# Relay220VAC.net
KiCad netlist of a schematic drawn in Altium Designer
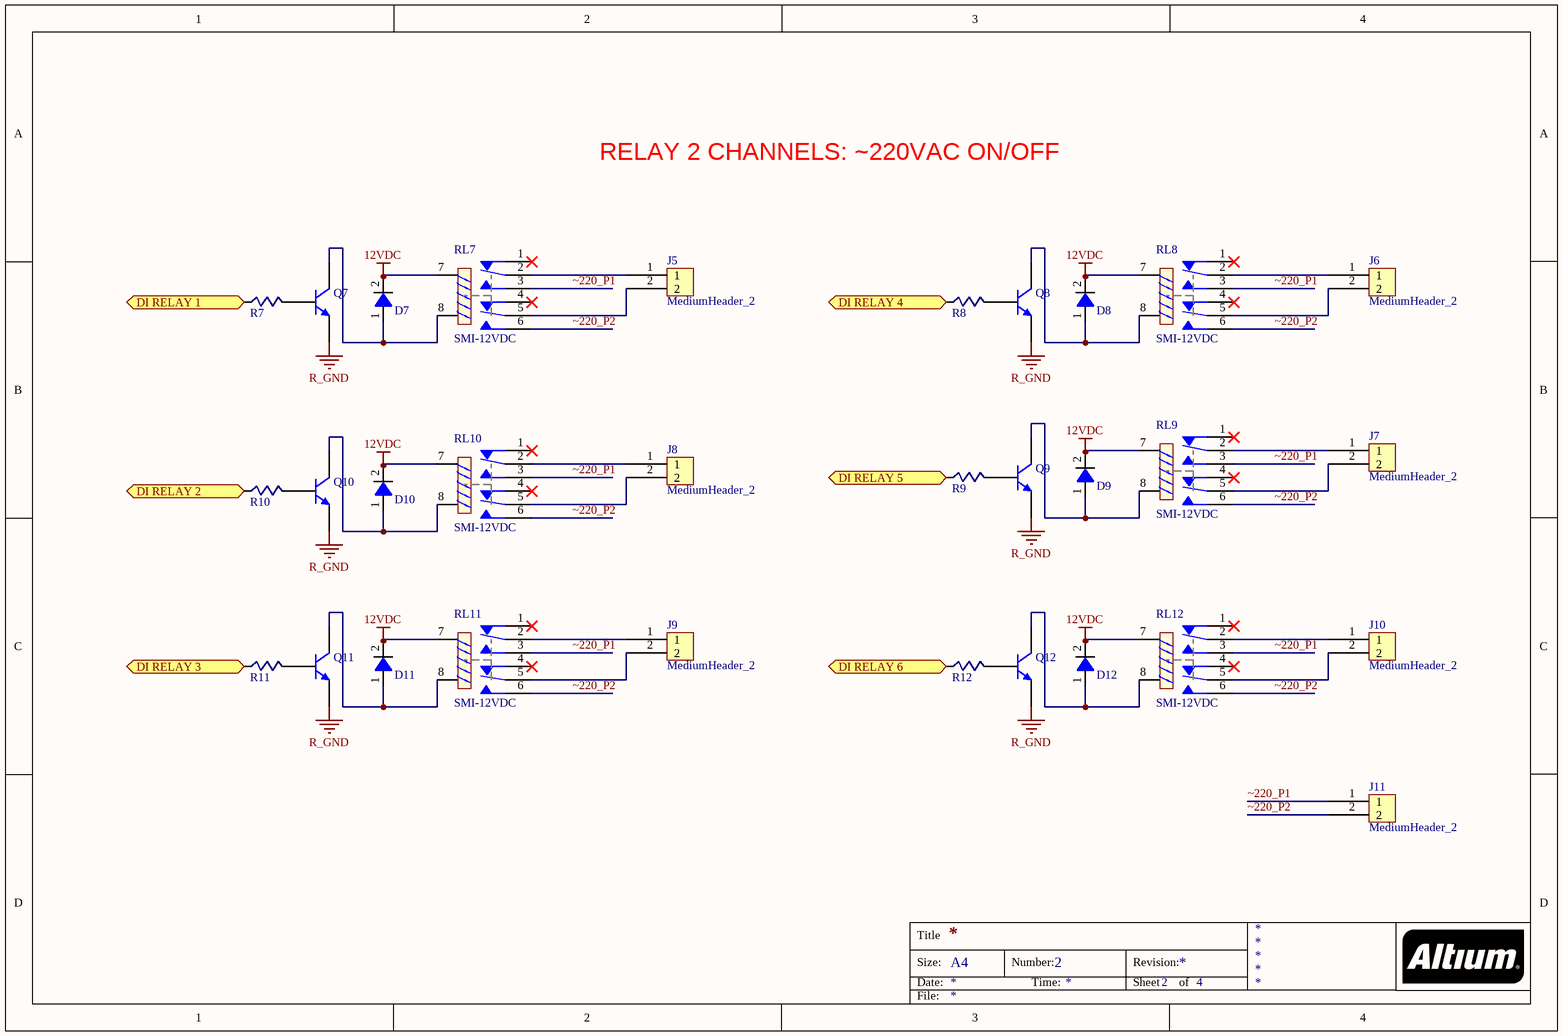
[diagram p0: Relay220VAC.SchDoc]

(export (version "E")
  (design (tool "Eeschema 10.0.6"))
  (components
    (comp (ref "D7")
      (value "M7 SMD")
      (footprint "Diode 1N4007 SMD")
      (description "DIODE GEN PURP 1KV 1A DO214AC")
      (libsource (lib "EngineersLife") (part "Diode_1N4007"))
    )
    (comp (ref "D8")
      (value "M7 SMD")
      (footprint "Diode 1N4007 SMD")
      (description "DIODE GEN PURP 1KV 1A DO214AC")
      (libsource (lib "EngineersLife") (part "Diode_1N4007"))
    )
    (comp (ref "D9")
      (value "M7 SMD")
      (footprint "Diode 1N4007 SMD")
      (description "DIODE GEN PURP 1KV 1A DO214AC")
      (libsource (lib "EngineersLife") (part "Diode_1N4007"))
    )
    (comp (ref "D10")
      (value "M7 SMD")
      (footprint "Diode 1N4007 SMD")
      (description "DIODE GEN PURP 1KV 1A DO214AC")
      (libsource (lib "EngineersLife") (part "Diode_1N4007"))
    )
    (comp (ref "D11")
      (value "M7 SMD")
      (footprint "Diode 1N4007 SMD")
      (description "DIODE GEN PURP 1KV 1A DO214AC")
      (libsource (lib "EngineersLife") (part "Diode_1N4007"))
    )
    (comp (ref "D12")
      (value "M7 SMD")
      (footprint "Diode 1N4007 SMD")
      (description "DIODE GEN PURP 1KV 1A DO214AC")
      (libsource (lib "EngineersLife") (part "Diode_1N4007"))
    )
    (comp (ref "J5")
      (value "MediumHeader_2")
      (footprint "Medium - Header 2")
      (libsource (lib "EngineersLife") (part "MediumHeader_2"))
    )
    (comp (ref "J6")
      (value "MediumHeader_2")
      (footprint "Medium - Header 2")
      (libsource (lib "EngineersLife") (part "MediumHeader_2"))
    )
    (comp (ref "J7")
      (value "MediumHeader_2")
      (footprint "Medium - Header 2")
      (libsource (lib "EngineersLife") (part "MediumHeader_2"))
    )
    (comp (ref "J8")
      (value "MediumHeader_2")
      (footprint "Medium - Header 2")
      (libsource (lib "EngineersLife") (part "MediumHeader_2"))
    )
    (comp (ref "J9")
      (value "MediumHeader_2")
      (footprint "Medium - Header 2")
      (libsource (lib "EngineersLife") (part "MediumHeader_2"))
    )
    (comp (ref "J10")
      (value "MediumHeader_2")
      (footprint "Medium - Header 2")
      (libsource (lib "EngineersLife") (part "MediumHeader_2"))
    )
    (comp (ref "J11")
      (value "MediumHeader_2")
      (footprint "Medium - Header 2")
      (libsource (lib "EngineersLife") (part "MediumHeader_2"))
    )
    (comp (ref "Q7")
      (value "MMBT3904")
      (footprint "SOT23_L_MOD")
      (description "TRANSISTOR GP NPN AMP SOT-23")
      (fields (field (name "PUBLISHER") "Altium Limited"))
      (libsource (lib "EngineersLife") (part "MMBT3904"))
    )
    (comp (ref "Q8")
      (value "MMBT3904")
      (footprint "SOT23_L_MOD")
      (description "TRANSISTOR GP NPN AMP SOT-23")
      (fields (field (name "PUBLISHER") "Altium Limited"))
      (libsource (lib "EngineersLife") (part "MMBT3904"))
    )
    (comp (ref "Q9")
      (value "MMBT3904")
      (footprint "SOT23_L_MOD")
      (description "TRANSISTOR GP NPN AMP SOT-23")
      (fields (field (name "PUBLISHER") "Altium Limited"))
      (libsource (lib "EngineersLife") (part "MMBT3904"))
    )
    (comp (ref "Q10")
      (value "MMBT3904")
      (footprint "SOT23_L_MOD")
      (description "TRANSISTOR GP NPN AMP SOT-23")
      (fields (field (name "PUBLISHER") "Altium Limited"))
      (libsource (lib "EngineersLife") (part "MMBT3904"))
    )
    (comp (ref "Q11")
      (value "MMBT3904")
      (footprint "SOT23_L_MOD")
      (description "TRANSISTOR GP NPN AMP SOT-23")
      (fields (field (name "PUBLISHER") "Altium Limited"))
      (libsource (lib "EngineersLife") (part "MMBT3904"))
    )
    (comp (ref "Q12")
      (value "MMBT3904")
      (footprint "SOT23_L_MOD")
      (description "TRANSISTOR GP NPN AMP SOT-23")
      (fields (field (name "PUBLISHER") "Altium Limited"))
      (libsource (lib "EngineersLife") (part "MMBT3904"))
    )
    (comp (ref "R7")
      (value "R_1K_0603")
      (footprint "RES-SMD-0603")
      (description "RES 1K OHM 1/10W 1% 0603 SMD")
      (libsource (lib "EngineersLife") (part "RES0603_1K"))
    )
    (comp (ref "R8")
      (value "R_1K_0603")
      (footprint "RES-SMD-0603")
      (description "RES 1K OHM 1/10W 1% 0603 SMD")
      (libsource (lib "EngineersLife") (part "RES0603_1K"))
    )
    (comp (ref "R9")
      (value "R_1K_0603")
      (footprint "RES-SMD-0603")
      (description "RES 1K OHM 1/10W 1% 0603 SMD")
      (libsource (lib "EngineersLife") (part "RES0603_1K"))
    )
    (comp (ref "R10")
      (value "R_1K_0603")
      (footprint "RES-SMD-0603")
      (description "RES 1K OHM 1/10W 1% 0603 SMD")
      (libsource (lib "EngineersLife") (part "RES0603_1K"))
    )
    (comp (ref "R11")
      (value "R_1K_0603")
      (footprint "RES-SMD-0603")
      (description "RES 1K OHM 1/10W 1% 0603 SMD")
      (libsource (lib "EngineersLife") (part "RES0603_1K"))
    )
    (comp (ref "R12")
      (value "R_1K_0603")
      (footprint "RES-SMD-0603")
      (description "RES 1K OHM 1/10W 1% 0603 SMD")
      (libsource (lib "EngineersLife") (part "RES0603_1K"))
    )
    (comp (ref "RL7")
      (value "SMI-12VDC")
      (footprint "RELAY SMI-2P")
      (description "Relay 12VDC, 2 channel")
      (libsource (lib "EngineersLife") (part "RELAY SMI-2P"))
    )
    (comp (ref "RL8")
      (value "SMI-12VDC")
      (footprint "RELAY SMI-2P")
      (description "Relay 12VDC, 2 channel")
      (libsource (lib "EngineersLife") (part "RELAY SMI-2P"))
    )
    (comp (ref "RL9")
      (value "SMI-12VDC")
      (footprint "RELAY SMI-2P")
      (description "Relay 12VDC, 2 channel")
      (libsource (lib "EngineersLife") (part "RELAY SMI-2P"))
    )
    (comp (ref "RL10")
      (value "SMI-12VDC")
      (footprint "RELAY SMI-2P")
      (description "Relay 12VDC, 2 channel")
      (libsource (lib "EngineersLife") (part "RELAY SMI-2P"))
    )
    (comp (ref "RL11")
      (value "SMI-12VDC")
      (footprint "RELAY SMI-2P")
      (description "Relay 12VDC, 2 channel")
      (libsource (lib "EngineersLife") (part "RELAY SMI-2P"))
    )
    (comp (ref "RL12")
      (value "SMI-12VDC")
      (footprint "RELAY SMI-2P")
      (description "Relay 12VDC, 2 channel")
      (libsource (lib "EngineersLife") (part "RELAY SMI-2P"))
    )
  )
  (nets
    (net (code "1") (name "/DI RELAY 1") (class "Default")
      (node (ref "R7") (pin "1") (pinfunction "1_1") (pintype "passive"))
    )
    (net (code "2") (name "/DI RELAY 2") (class "Default")
      (node (ref "R10") (pin "1") (pinfunction "1_1") (pintype "passive"))
    )
    (net (code "3") (name "/DI RELAY 3") (class "Default")
      (node (ref "R11") (pin "1") (pinfunction "1_1") (pintype "passive"))
    )
    (net (code "4") (name "/DI RELAY 4") (class "Default")
      (node (ref "R8") (pin "1") (pinfunction "1_1") (pintype "passive"))
    )
    (net (code "5") (name "/DI RELAY 5") (class "Default")
      (node (ref "R9") (pin "1") (pinfunction "1_1") (pintype "passive"))
    )
    (net (code "6") (name "/DI RELAY 6") (class "Default")
      (node (ref "R12") (pin "1") (pinfunction "1_1") (pintype "passive"))
    )
    (net (code "7") (name "/~220_P1") (class "Default")
      (node (ref "J11") (pin "1") (pinfunction "1_1") (pintype "passive"))
      (node (ref "RL10") (pin "3") (pinfunction "3_3") (pintype "passive"))
      (node (ref "RL11") (pin "3") (pinfunction "3_3") (pintype "passive"))
      (node (ref "RL12") (pin "3") (pinfunction "3_3") (pintype "passive"))
      (node (ref "RL7") (pin "3") (pinfunction "3_3") (pintype "passive"))
      (node (ref "RL8") (pin "3") (pinfunction "3_3") (pintype "passive"))
      (node (ref "RL9") (pin "3") (pinfunction "3_3") (pintype "passive"))
    )
    (net (code "8") (name "/~220_P2") (class "Default")
      (node (ref "J11") (pin "2") (pinfunction "2_2") (pintype "passive"))
      (node (ref "RL10") (pin "6") (pinfunction "6_6") (pintype "passive"))
      (node (ref "RL11") (pin "6") (pinfunction "6_6") (pintype "passive"))
      (node (ref "RL12") (pin "6") (pinfunction "6_6") (pintype "passive"))
      (node (ref "RL7") (pin "6") (pinfunction "6_6") (pintype "passive"))
      (node (ref "RL8") (pin "6") (pinfunction "6_6") (pintype "passive"))
      (node (ref "RL9") (pin "6") (pinfunction "6_6") (pintype "passive"))
    )
    (net (code "9") (name "12VDC") (class "Default")
      (node (ref "D10") (pin "2") (pinfunction "4_2") (pintype "passive"))
      (node (ref "D11") (pin "2") (pinfunction "4_2") (pintype "passive"))
      (node (ref "D12") (pin "2") (pinfunction "4_2") (pintype "passive"))
      (node (ref "D7") (pin "2") (pinfunction "4_2") (pintype "passive"))
      (node (ref "D8") (pin "2") (pinfunction "4_2") (pintype "passive"))
      (node (ref "D9") (pin "2") (pinfunction "4_2") (pintype "passive"))
      (node (ref "RL10") (pin "7") (pinfunction "7_7") (pintype "passive"))
      (node (ref "RL11") (pin "7") (pinfunction "7_7") (pintype "passive"))
      (node (ref "RL12") (pin "7") (pinfunction "7_7") (pintype "passive"))
      (node (ref "RL7") (pin "7") (pinfunction "7_7") (pintype "passive"))
      (node (ref "RL8") (pin "7") (pinfunction "7_7") (pintype "passive"))
      (node (ref "RL9") (pin "7") (pinfunction "7_7") (pintype "passive"))
    )
    (net (code "10") (name "Net-(D7-3)") (class "Default")
      (node (ref "D7") (pin "1") (pinfunction "3_1") (pintype "passive"))
      (node (ref "Q7") (pin "3") (pinfunction "C_3") (pintype "passive"))
      (node (ref "RL7") (pin "8") (pinfunction "8_8") (pintype "passive"))
    )
    (net (code "11") (name "Net-(D8-3)") (class "Default")
      (node (ref "D8") (pin "1") (pinfunction "3_1") (pintype "passive"))
      (node (ref "Q8") (pin "3") (pinfunction "C_3") (pintype "passive"))
      (node (ref "RL8") (pin "8") (pinfunction "8_8") (pintype "passive"))
    )
    (net (code "12") (name "Net-(D9-3)") (class "Default")
      (node (ref "D9") (pin "1") (pinfunction "3_1") (pintype "passive"))
      (node (ref "Q9") (pin "3") (pinfunction "C_3") (pintype "passive"))
      (node (ref "RL9") (pin "8") (pinfunction "8_8") (pintype "passive"))
    )
    (net (code "13") (name "Net-(D10-3)") (class "Default")
      (node (ref "D10") (pin "1") (pinfunction "3_1") (pintype "passive"))
      (node (ref "Q10") (pin "3") (pinfunction "C_3") (pintype "passive"))
      (node (ref "RL10") (pin "8") (pinfunction "8_8") (pintype "passive"))
    )
    (net (code "14") (name "Net-(D11-3)") (class "Default")
      (node (ref "D11") (pin "1") (pinfunction "3_1") (pintype "passive"))
      (node (ref "Q11") (pin "3") (pinfunction "C_3") (pintype "passive"))
      (node (ref "RL11") (pin "8") (pinfunction "8_8") (pintype "passive"))
    )
    (net (code "15") (name "Net-(D12-3)") (class "Default")
      (node (ref "D12") (pin "1") (pinfunction "3_1") (pintype "passive"))
      (node (ref "Q12") (pin "3") (pinfunction "C_3") (pintype "passive"))
      (node (ref "RL12") (pin "8") (pinfunction "8_8") (pintype "passive"))
    )
    (net (code "16") (name "Net-(J5-Pad1)") (class "Default")
      (node (ref "J5") (pin "1") (pinfunction "1_1") (pintype "passive"))
      (node (ref "RL7") (pin "2") (pinfunction "2_2") (pintype "passive"))
    )
    (net (code "17") (name "Net-(J5-Pad2)") (class "Default")
      (node (ref "J5") (pin "2") (pinfunction "2_2") (pintype "passive"))
      (node (ref "RL7") (pin "5") (pinfunction "5_5") (pintype "passive"))
    )
    (net (code "18") (name "Net-(J6-Pad1)") (class "Default")
      (node (ref "J6") (pin "1") (pinfunction "1_1") (pintype "passive"))
      (node (ref "RL8") (pin "2") (pinfunction "2_2") (pintype "passive"))
    )
    (net (code "19") (name "Net-(J6-Pad2)") (class "Default")
      (node (ref "J6") (pin "2") (pinfunction "2_2") (pintype "passive"))
      (node (ref "RL8") (pin "5") (pinfunction "5_5") (pintype "passive"))
    )
    (net (code "20") (name "Net-(J7-Pad1)") (class "Default")
      (node (ref "J7") (pin "1") (pinfunction "1_1") (pintype "passive"))
      (node (ref "RL9") (pin "2") (pinfunction "2_2") (pintype "passive"))
    )
    (net (code "21") (name "Net-(J7-Pad2)") (class "Default")
      (node (ref "J7") (pin "2") (pinfunction "2_2") (pintype "passive"))
      (node (ref "RL9") (pin "5") (pinfunction "5_5") (pintype "passive"))
    )
    (net (code "22") (name "Net-(J8-Pad1)") (class "Default")
      (node (ref "J8") (pin "1") (pinfunction "1_1") (pintype "passive"))
      (node (ref "RL10") (pin "2") (pinfunction "2_2") (pintype "passive"))
    )
    (net (code "23") (name "Net-(J8-Pad2)") (class "Default")
      (node (ref "J8") (pin "2") (pinfunction "2_2") (pintype "passive"))
      (node (ref "RL10") (pin "5") (pinfunction "5_5") (pintype "passive"))
    )
    (net (code "24") (name "Net-(J9-Pad1)") (class "Default")
      (node (ref "J9") (pin "1") (pinfunction "1_1") (pintype "passive"))
      (node (ref "RL11") (pin "2") (pinfunction "2_2") (pintype "passive"))
    )
    (net (code "25") (name "Net-(J9-Pad2)") (class "Default")
      (node (ref "J9") (pin "2") (pinfunction "2_2") (pintype "passive"))
      (node (ref "RL11") (pin "5") (pinfunction "5_5") (pintype "passive"))
    )
    (net (code "26") (name "Net-(J10-Pad1)") (class "Default")
      (node (ref "J10") (pin "1") (pinfunction "1_1") (pintype "passive"))
      (node (ref "RL12") (pin "2") (pinfunction "2_2") (pintype "passive"))
    )
    (net (code "27") (name "Net-(J10-Pad2)") (class "Default")
      (node (ref "J10") (pin "2") (pinfunction "2_2") (pintype "passive"))
      (node (ref "RL12") (pin "5") (pinfunction "5_5") (pintype "passive"))
    )
    (net (code "28") (name "Net-(Q7-B)") (class "Default")
      (node (ref "Q7") (pin "1") (pinfunction "B_1") (pintype "passive"))
      (node (ref "R7") (pin "2") (pinfunction "2_2") (pintype "passive"))
    )
    (net (code "29") (name "Net-(Q8-B)") (class "Default")
      (node (ref "Q8") (pin "1") (pinfunction "B_1") (pintype "passive"))
      (node (ref "R8") (pin "2") (pinfunction "2_2") (pintype "passive"))
    )
    (net (code "30") (name "Net-(Q9-B)") (class "Default")
      (node (ref "Q9") (pin "1") (pinfunction "B_1") (pintype "passive"))
      (node (ref "R9") (pin "2") (pinfunction "2_2") (pintype "passive"))
    )
    (net (code "31") (name "Net-(Q10-B)") (class "Default")
      (node (ref "Q10") (pin "1") (pinfunction "B_1") (pintype "passive"))
      (node (ref "R10") (pin "2") (pinfunction "2_2") (pintype "passive"))
    )
    (net (code "32") (name "Net-(Q11-B)") (class "Default")
      (node (ref "Q11") (pin "1") (pinfunction "B_1") (pintype "passive"))
      (node (ref "R11") (pin "2") (pinfunction "2_2") (pintype "passive"))
    )
    (net (code "33") (name "Net-(Q12-B)") (class "Default")
      (node (ref "Q12") (pin "1") (pinfunction "B_1") (pintype "passive"))
      (node (ref "R12") (pin "2") (pinfunction "2_2") (pintype "passive"))
    )
    (net (code "34") (name "R_GND") (class "Default")
      (node (ref "Q10") (pin "2") (pinfunction "E_2") (pintype "passive"))
      (node (ref "Q11") (pin "2") (pinfunction "E_2") (pintype "passive"))
      (node (ref "Q12") (pin "2") (pinfunction "E_2") (pintype "passive"))
      (node (ref "Q7") (pin "2") (pinfunction "E_2") (pintype "passive"))
      (node (ref "Q8") (pin "2") (pinfunction "E_2") (pintype "passive"))
      (node (ref "Q9") (pin "2") (pinfunction "E_2") (pintype "passive"))
    )
    (net (code "35") (name "unconnected-(RL7-Pad1)") (class "Default")
      (node (ref "RL7") (pin "1") (pinfunction "1_1") (pintype "passive+no_connect"))
    )
    (net (code "36") (name "unconnected-(RL7-Pad4)") (class "Default")
      (node (ref "RL7") (pin "4") (pinfunction "4_4") (pintype "passive+no_connect"))
    )
    (net (code "37") (name "unconnected-(RL8-Pad1)") (class "Default")
      (node (ref "RL8") (pin "1") (pinfunction "1_1") (pintype "passive+no_connect"))
    )
    (net (code "38") (name "unconnected-(RL8-Pad4)") (class "Default")
      (node (ref "RL8") (pin "4") (pinfunction "4_4") (pintype "passive+no_connect"))
    )
    (net (code "39") (name "unconnected-(RL9-Pad1)") (class "Default")
      (node (ref "RL9") (pin "1") (pinfunction "1_1") (pintype "passive+no_connect"))
    )
    (net (code "40") (name "unconnected-(RL9-Pad4)") (class "Default")
      (node (ref "RL9") (pin "4") (pinfunction "4_4") (pintype "passive+no_connect"))
    )
    (net (code "41") (name "unconnected-(RL10-Pad1)") (class "Default")
      (node (ref "RL10") (pin "1") (pinfunction "1_1") (pintype "passive+no_connect"))
    )
    (net (code "42") (name "unconnected-(RL10-Pad4)") (class "Default")
      (node (ref "RL10") (pin "4") (pinfunction "4_4") (pintype "passive+no_connect"))
    )
    (net (code "43") (name "unconnected-(RL11-Pad1)") (class "Default")
      (node (ref "RL11") (pin "1") (pinfunction "1_1") (pintype "passive+no_connect"))
    )
    (net (code "44") (name "unconnected-(RL11-Pad4)") (class "Default")
      (node (ref "RL11") (pin "4") (pinfunction "4_4") (pintype "passive+no_connect"))
    )
    (net (code "45") (name "unconnected-(RL12-Pad1)") (class "Default")
      (node (ref "RL12") (pin "1") (pinfunction "1_1") (pintype "passive+no_connect"))
    )
    (net (code "46") (name "unconnected-(RL12-Pad4)") (class "Default")
      (node (ref "RL12") (pin "4") (pinfunction "4_4") (pintype "passive+no_connect"))
    )
  )
)
